# ENC_MPX_V0_1.net
KiCad netlist of a schematic drawn in EAGLE
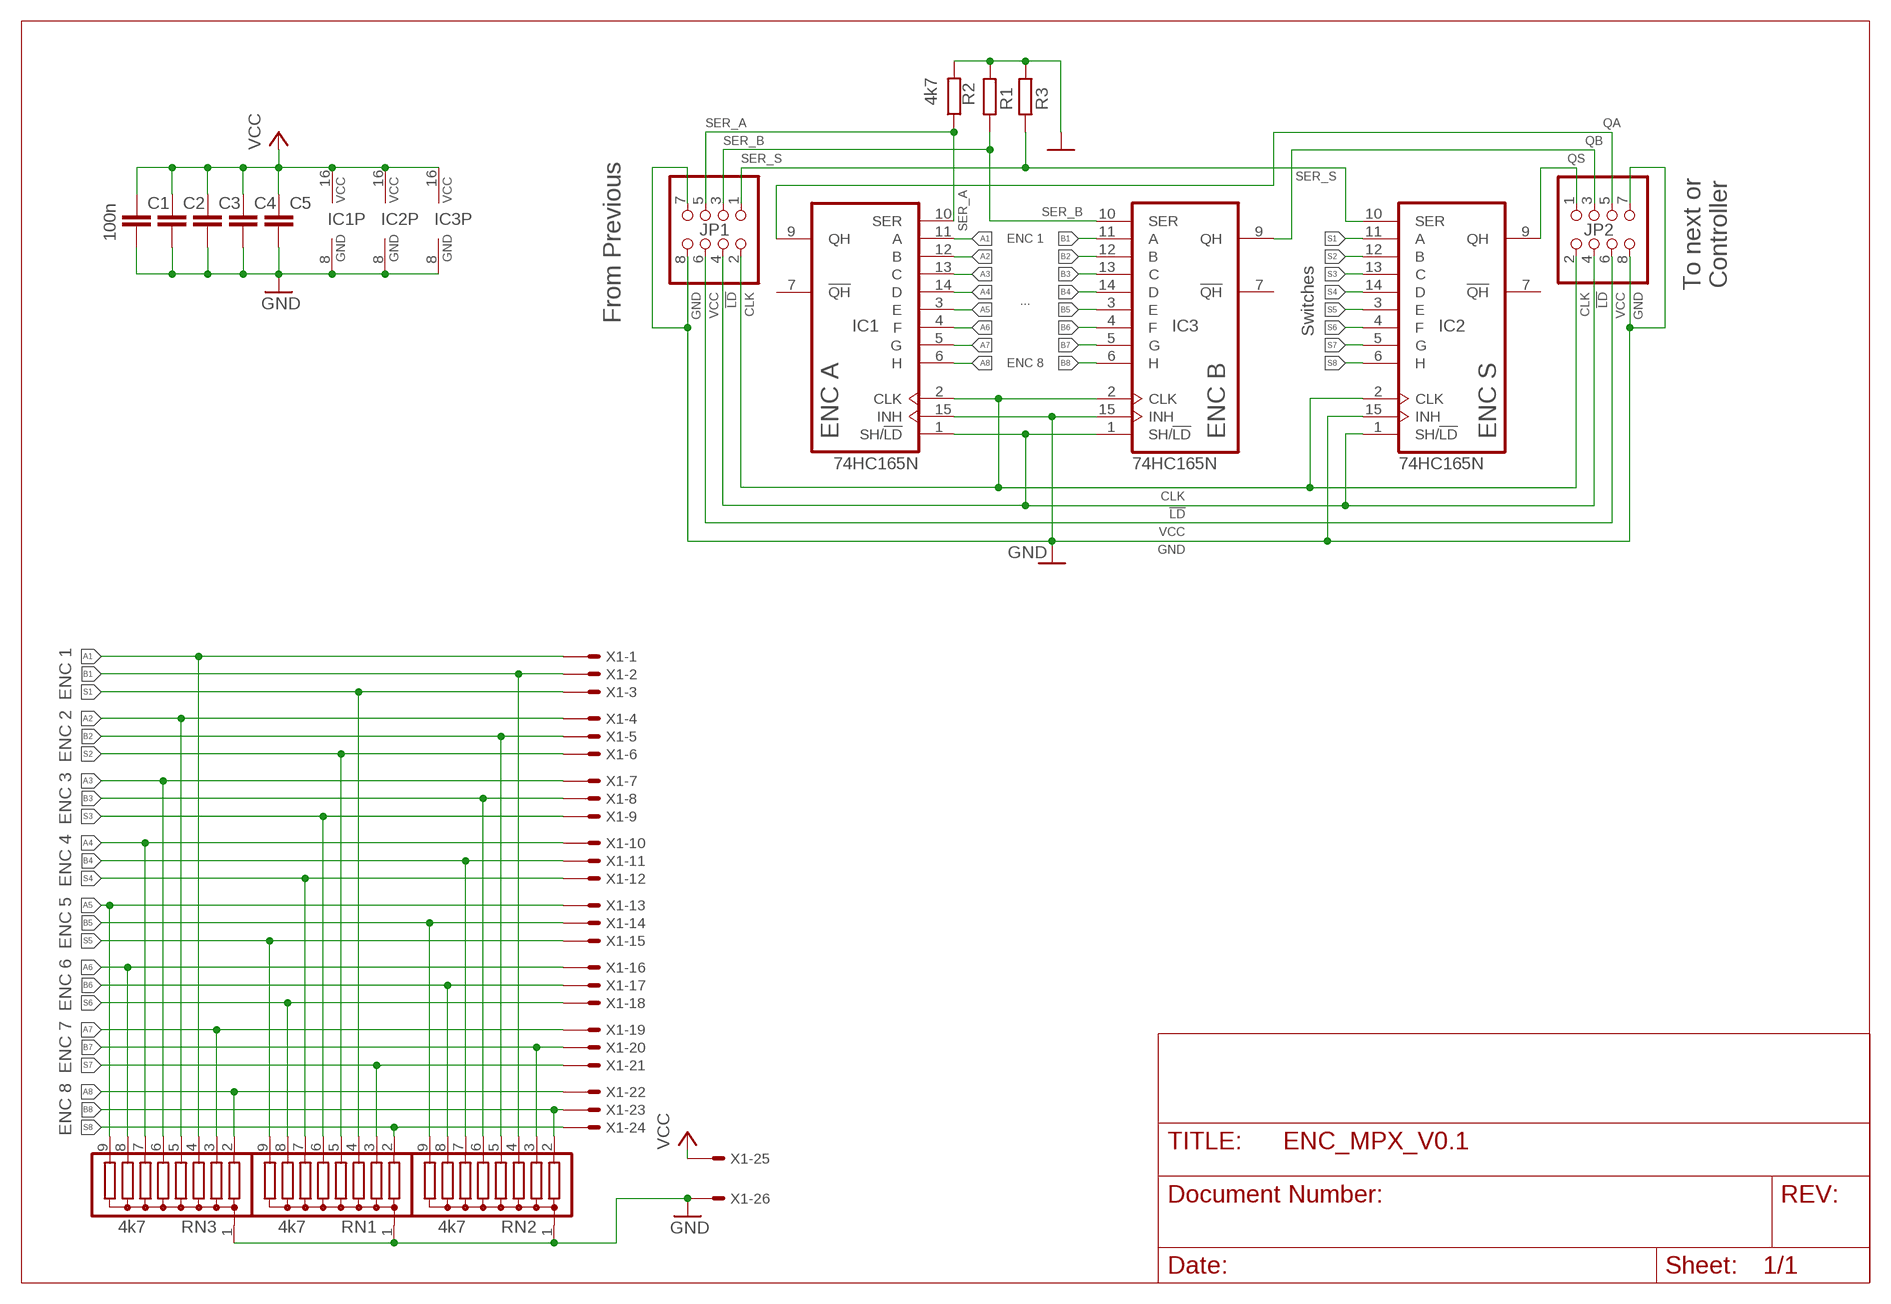
[diagram p0: schematic, sheet 1]

(export (version "E")
  (design (tool "Eeschema 10.0.6"))
  (components
    (comp (ref "C1")
      (value "100n")
      (footprint "eagle-import:C025-025X050")
      (libsource (lib "eagle-import") (part "C-EU025-025X050"))
    )
    (comp (ref "C2")
      (value "100n")
      (footprint "eagle-import:C025-025X050")
      (libsource (lib "eagle-import") (part "C-EU025-025X050"))
    )
    (comp (ref "C3")
      (value "100n")
      (footprint "eagle-import:C025-025X050")
      (libsource (lib "eagle-import") (part "C-EU025-025X050"))
    )
    (comp (ref "C4")
      (value "100n")
      (footprint "eagle-import:C025-025X050")
      (libsource (lib "eagle-import") (part "C-EU025-025X050"))
    )
    (comp (ref "C5")
      (value "100n")
      (footprint "eagle-import:C025-025X050")
      (libsource (lib "eagle-import") (part "C-EU025-025X050"))
    )
    (comp (ref "IC1")
      (value "74HC165N")
      (footprint "eagle-import:DIL16")
      (libsource (lib "eagle-import") (part "74165NHC"))
    )
    (comp (ref "IC2")
      (value "74HC165N")
      (footprint "eagle-import:DIL16")
      (libsource (lib "eagle-import") (part "74165NHC"))
    )
    (comp (ref "IC3")
      (value "74HC165N")
      (footprint "eagle-import:DIL16")
      (libsource (lib "eagle-import") (part "74165NHC"))
    )
    (comp (ref "JP1")
      (value "PINHD-2X4")
      (footprint "eagle-import:2X04")
      (libsource (lib "eagle-import") (part "PINHD-2X4"))
    )
    (comp (ref "JP2")
      (value "PINHD-2X4")
      (footprint "eagle-import:2X04")
      (libsource (lib "eagle-import") (part "PINHD-2X4"))
    )
    (comp (ref "R1")
      (value "4k7")
      (footprint "eagle-import:0204_7")
      (libsource (lib "eagle-import") (part "R-EU_0204/7"))
    )
    (comp (ref "R2")
      (value "4k7")
      (footprint "eagle-import:0204_7")
      (libsource (lib "eagle-import") (part "R-EU_0204/7"))
    )
    (comp (ref "R3")
      (value "4k7")
      (footprint "eagle-import:0204_7")
      (libsource (lib "eagle-import") (part "R-EU_0204/7"))
    )
    (comp (ref "RN1")
      (value "4k7")
      (footprint "eagle-import:SIL9")
      (libsource (lib "eagle-import") (part "G08R"))
    )
    (comp (ref "RN2")
      (value "4k7")
      (footprint "eagle-import:SIL9")
      (libsource (lib "eagle-import") (part "G08R"))
    )
    (comp (ref "RN3")
      (value "4k7")
      (footprint "eagle-import:SIL9")
      (libsource (lib "eagle-import") (part "G08R"))
    )
    (comp (ref "X1")
      (value "057-026-1")
      (footprint "eagle-import:057-026-1")
      (libsource (lib "eagle-import") (part "057-026-1"))
    )
  )
  (nets
    (net (code "1") (name "/CLK") (class "Default")
      (node (ref "IC1") (pin "2") (pinfunction "CLK_2") (pintype "input"))
      (node (ref "IC2") (pin "2") (pinfunction "CLK_2") (pintype "input"))
      (node (ref "IC3") (pin "2") (pinfunction "CLK_2") (pintype "input"))
      (node (ref "JP1") (pin "2") (pinfunction "2_2") (pintype "passive"))
      (node (ref "JP2") (pin "2") (pinfunction "2_2") (pintype "passive"))
    )
    (net (code "2") (name "/QA") (class "Default")
      (node (ref "IC1") (pin "9") (pinfunction "QH_9") (pintype "output"))
      (node (ref "JP2") (pin "5") (pinfunction "5_5") (pintype "passive"))
    )
    (net (code "3") (name "/QB") (class "Default")
      (node (ref "IC3") (pin "9") (pinfunction "QH_9") (pintype "output"))
      (node (ref "JP2") (pin "3") (pinfunction "3_3") (pintype "passive"))
    )
    (net (code "4") (name "/QS") (class "Default")
      (node (ref "IC2") (pin "9") (pinfunction "QH_9") (pintype "output"))
      (node (ref "JP2") (pin "1") (pinfunction "1_1") (pintype "passive"))
    )
    (net (code "5") (name "/SER_A") (class "Default")
      (node (ref "IC1") (pin "10") (pinfunction "SER_10") (pintype "input"))
      (node (ref "JP1") (pin "5") (pinfunction "5_5") (pintype "passive"))
      (node (ref "R2") (pin "1") (pinfunction "1_1") (pintype "passive"))
    )
    (net (code "6") (name "/SER_B") (class "Default")
      (node (ref "IC3") (pin "10") (pinfunction "SER_10") (pintype "input"))
      (node (ref "JP1") (pin "3") (pinfunction "3_3") (pintype "passive"))
      (node (ref "R1") (pin "2") (pinfunction "2_2") (pintype "passive"))
    )
    (net (code "7") (name "/SER_S") (class "Default")
      (node (ref "IC2") (pin "10") (pinfunction "SER_10") (pintype "input"))
      (node (ref "JP1") (pin "1") (pinfunction "1_1") (pintype "passive"))
      (node (ref "R3") (pin "2") (pinfunction "2_2") (pintype "passive"))
    )
    (net (code "8") (name "/~{LD}") (class "Default")
      (node (ref "IC1") (pin "1") (pinfunction "SH/~{LD}_1") (pintype "input"))
      (node (ref "IC2") (pin "1") (pinfunction "SH/~{LD}_1") (pintype "input"))
      (node (ref "IC3") (pin "1") (pinfunction "SH/~{LD}_1") (pintype "input"))
      (node (ref "JP1") (pin "4") (pinfunction "4_4") (pintype "passive"))
      (node (ref "JP2") (pin "4") (pinfunction "4_4") (pintype "passive"))
    )
    (net (code "9") (name "A1") (class "Default")
      (node (ref "IC1") (pin "11") (pinfunction "A_11") (pintype "input"))
      (node (ref "RN3") (pin "4") (pinfunction "4_4") (pintype "passive"))
      (node (ref "X1") (pin "1") (pinfunction "S_1") (pintype "passive"))
    )
    (net (code "10") (name "A2") (class "Default")
      (node (ref "IC1") (pin "12") (pinfunction "B_12") (pintype "input"))
      (node (ref "RN3") (pin "5") (pinfunction "5_5") (pintype "passive"))
      (node (ref "X1") (pin "4") (pinfunction "S_4") (pintype "passive"))
    )
    (net (code "11") (name "A3") (class "Default")
      (node (ref "IC1") (pin "13") (pinfunction "C_13") (pintype "input"))
      (node (ref "RN3") (pin "6") (pinfunction "6_6") (pintype "passive"))
      (node (ref "X1") (pin "7") (pinfunction "S_7") (pintype "passive"))
    )
    (net (code "12") (name "A4") (class "Default")
      (node (ref "IC1") (pin "14") (pinfunction "D_14") (pintype "input"))
      (node (ref "RN3") (pin "7") (pinfunction "7_7") (pintype "passive"))
      (node (ref "X1") (pin "10") (pinfunction "S_10") (pintype "passive"))
    )
    (net (code "13") (name "A5") (class "Default")
      (node (ref "IC1") (pin "3") (pinfunction "E_3") (pintype "input"))
      (node (ref "RN3") (pin "9") (pinfunction "9_9") (pintype "passive"))
      (node (ref "X1") (pin "13") (pinfunction "S_13") (pintype "passive"))
    )
    (net (code "14") (name "A6") (class "Default")
      (node (ref "IC1") (pin "4") (pinfunction "F_4") (pintype "input"))
      (node (ref "RN3") (pin "8") (pinfunction "8_8") (pintype "passive"))
      (node (ref "X1") (pin "16") (pinfunction "S_16") (pintype "passive"))
    )
    (net (code "15") (name "A7") (class "Default")
      (node (ref "IC1") (pin "5") (pinfunction "G_5") (pintype "input"))
      (node (ref "RN3") (pin "3") (pinfunction "3_3") (pintype "passive"))
      (node (ref "X1") (pin "19") (pinfunction "S_19") (pintype "passive"))
    )
    (net (code "16") (name "A8") (class "Default")
      (node (ref "IC1") (pin "6") (pinfunction "H_6") (pintype "input"))
      (node (ref "RN3") (pin "2") (pinfunction "2_2") (pintype "passive"))
      (node (ref "X1") (pin "22") (pinfunction "S_22") (pintype "passive"))
    )
    (net (code "17") (name "B1") (class "Default")
      (node (ref "IC3") (pin "11") (pinfunction "A_11") (pintype "input"))
      (node (ref "RN2") (pin "4") (pinfunction "4_4") (pintype "passive"))
      (node (ref "X1") (pin "2") (pinfunction "S_2") (pintype "passive"))
    )
    (net (code "18") (name "B2") (class "Default")
      (node (ref "IC3") (pin "12") (pinfunction "B_12") (pintype "input"))
      (node (ref "RN2") (pin "5") (pinfunction "5_5") (pintype "passive"))
      (node (ref "X1") (pin "5") (pinfunction "S_5") (pintype "passive"))
    )
    (net (code "19") (name "B3") (class "Default")
      (node (ref "IC3") (pin "13") (pinfunction "C_13") (pintype "input"))
      (node (ref "RN2") (pin "6") (pinfunction "6_6") (pintype "passive"))
      (node (ref "X1") (pin "8") (pinfunction "S_8") (pintype "passive"))
    )
    (net (code "20") (name "B4") (class "Default")
      (node (ref "IC3") (pin "14") (pinfunction "D_14") (pintype "input"))
      (node (ref "RN2") (pin "7") (pinfunction "7_7") (pintype "passive"))
      (node (ref "X1") (pin "11") (pinfunction "S_11") (pintype "passive"))
    )
    (net (code "21") (name "B5") (class "Default")
      (node (ref "IC3") (pin "3") (pinfunction "E_3") (pintype "input"))
      (node (ref "RN2") (pin "9") (pinfunction "9_9") (pintype "passive"))
      (node (ref "X1") (pin "14") (pinfunction "S_14") (pintype "passive"))
    )
    (net (code "22") (name "B6") (class "Default")
      (node (ref "IC3") (pin "4") (pinfunction "F_4") (pintype "input"))
      (node (ref "RN2") (pin "8") (pinfunction "8_8") (pintype "passive"))
      (node (ref "X1") (pin "17") (pinfunction "S_17") (pintype "passive"))
    )
    (net (code "23") (name "B7") (class "Default")
      (node (ref "IC3") (pin "5") (pinfunction "G_5") (pintype "input"))
      (node (ref "RN2") (pin "3") (pinfunction "3_3") (pintype "passive"))
      (node (ref "X1") (pin "20") (pinfunction "S_20") (pintype "passive"))
    )
    (net (code "24") (name "B8") (class "Default")
      (node (ref "IC3") (pin "6") (pinfunction "H_6") (pintype "input"))
      (node (ref "RN2") (pin "2") (pinfunction "2_2") (pintype "passive"))
      (node (ref "X1") (pin "23") (pinfunction "S_23") (pintype "passive"))
    )
    (net (code "25") (name "GND") (class "Default")
      (node (ref "C1") (pin "2") (pinfunction "2_2") (pintype "passive"))
      (node (ref "C2") (pin "2") (pinfunction "2_2") (pintype "passive"))
      (node (ref "C3") (pin "2") (pinfunction "2_2") (pintype "passive"))
      (node (ref "C4") (pin "2") (pinfunction "2_2") (pintype "passive"))
      (node (ref "C5") (pin "2") (pinfunction "2_2") (pintype "passive"))
      (node (ref "IC1") (pin "15") (pinfunction "INH_15") (pintype "input"))
      (node (ref "IC1") (pin "8") (pinfunction "GND_8") (pintype "power_in"))
      (node (ref "IC2") (pin "15") (pinfunction "INH_15") (pintype "input"))
      (node (ref "IC2") (pin "8") (pinfunction "GND_8") (pintype "power_in"))
      (node (ref "IC3") (pin "15") (pinfunction "INH_15") (pintype "input"))
      (node (ref "IC3") (pin "8") (pinfunction "GND_8") (pintype "power_in"))
      (node (ref "JP1") (pin "7") (pinfunction "7_7") (pintype "passive"))
      (node (ref "JP1") (pin "8") (pinfunction "8_8") (pintype "passive"))
      (node (ref "JP2") (pin "7") (pinfunction "7_7") (pintype "passive"))
      (node (ref "JP2") (pin "8") (pinfunction "8_8") (pintype "passive"))
      (node (ref "R1") (pin "1") (pinfunction "1_1") (pintype "passive"))
      (node (ref "R2") (pin "2") (pinfunction "2_2") (pintype "passive"))
      (node (ref "R3") (pin "1") (pinfunction "1_1") (pintype "passive"))
      (node (ref "RN1") (pin "1") (pinfunction "1_1") (pintype "passive"))
      (node (ref "RN2") (pin "1") (pinfunction "1_1") (pintype "passive"))
      (node (ref "RN3") (pin "1") (pinfunction "1_1") (pintype "passive"))
      (node (ref "X1") (pin "26") (pinfunction "S_26") (pintype "passive"))
    )
    (net (code "26") (name "S1") (class "Default")
      (node (ref "IC2") (pin "11") (pinfunction "A_11") (pintype "input"))
      (node (ref "RN1") (pin "4") (pinfunction "4_4") (pintype "passive"))
      (node (ref "X1") (pin "3") (pinfunction "S_3") (pintype "passive"))
    )
    (net (code "27") (name "S2") (class "Default")
      (node (ref "IC2") (pin "12") (pinfunction "B_12") (pintype "input"))
      (node (ref "RN1") (pin "5") (pinfunction "5_5") (pintype "passive"))
      (node (ref "X1") (pin "6") (pinfunction "S_6") (pintype "passive"))
    )
    (net (code "28") (name "S3") (class "Default")
      (node (ref "IC2") (pin "13") (pinfunction "C_13") (pintype "input"))
      (node (ref "RN1") (pin "6") (pinfunction "6_6") (pintype "passive"))
      (node (ref "X1") (pin "9") (pinfunction "S_9") (pintype "passive"))
    )
    (net (code "29") (name "S4") (class "Default")
      (node (ref "IC2") (pin "14") (pinfunction "D_14") (pintype "input"))
      (node (ref "RN1") (pin "7") (pinfunction "7_7") (pintype "passive"))
      (node (ref "X1") (pin "12") (pinfunction "S_12") (pintype "passive"))
    )
    (net (code "30") (name "S5") (class "Default")
      (node (ref "IC2") (pin "3") (pinfunction "E_3") (pintype "input"))
      (node (ref "RN1") (pin "9") (pinfunction "9_9") (pintype "passive"))
      (node (ref "X1") (pin "15") (pinfunction "S_15") (pintype "passive"))
    )
    (net (code "31") (name "S6") (class "Default")
      (node (ref "IC2") (pin "4") (pinfunction "F_4") (pintype "input"))
      (node (ref "RN1") (pin "8") (pinfunction "8_8") (pintype "passive"))
      (node (ref "X1") (pin "18") (pinfunction "S_18") (pintype "passive"))
    )
    (net (code "32") (name "S7") (class "Default")
      (node (ref "IC2") (pin "5") (pinfunction "G_5") (pintype "input"))
      (node (ref "RN1") (pin "3") (pinfunction "3_3") (pintype "passive"))
      (node (ref "X1") (pin "21") (pinfunction "S_21") (pintype "passive"))
    )
    (net (code "33") (name "S8") (class "Default")
      (node (ref "IC2") (pin "6") (pinfunction "H_6") (pintype "input"))
      (node (ref "RN1") (pin "2") (pinfunction "2_2") (pintype "passive"))
      (node (ref "X1") (pin "24") (pinfunction "S_24") (pintype "passive"))
    )
    (net (code "34") (name "VCC") (class "Default")
      (node (ref "C1") (pin "1") (pinfunction "1_1") (pintype "passive"))
      (node (ref "C2") (pin "1") (pinfunction "1_1") (pintype "passive"))
      (node (ref "C3") (pin "1") (pinfunction "1_1") (pintype "passive"))
      (node (ref "C4") (pin "1") (pinfunction "1_1") (pintype "passive"))
      (node (ref "C5") (pin "1") (pinfunction "1_1") (pintype "passive"))
      (node (ref "IC1") (pin "16") (pinfunction "VCC_16") (pintype "power_in"))
      (node (ref "IC2") (pin "16") (pinfunction "VCC_16") (pintype "power_in"))
      (node (ref "IC3") (pin "16") (pinfunction "VCC_16") (pintype "power_in"))
      (node (ref "JP1") (pin "6") (pinfunction "6_6") (pintype "passive"))
      (node (ref "JP2") (pin "6") (pinfunction "6_6") (pintype "passive"))
      (node (ref "X1") (pin "25") (pinfunction "S_25") (pintype "passive"))
    )
    (net (code "35") (name "unconnected-(IC1A-~{QH}-Pad7)") (class "Default")
      (node (ref "IC1") (pin "7") (pinfunction "~{QH}_7") (pintype "output"))
    )
    (net (code "36") (name "unconnected-(IC2A-~{QH}-Pad7)") (class "Default")
      (node (ref "IC2") (pin "7") (pinfunction "~{QH}_7") (pintype "output"))
    )
    (net (code "37") (name "unconnected-(IC3A-~{QH}-Pad7)") (class "Default")
      (node (ref "IC3") (pin "7") (pinfunction "~{QH}_7") (pintype "output"))
    )
  )
)
